# SCH_Stimulus-Shield-_GroeiAcademie-Frame.net
KiCad netlist of a schematic drawn in EasyEDA
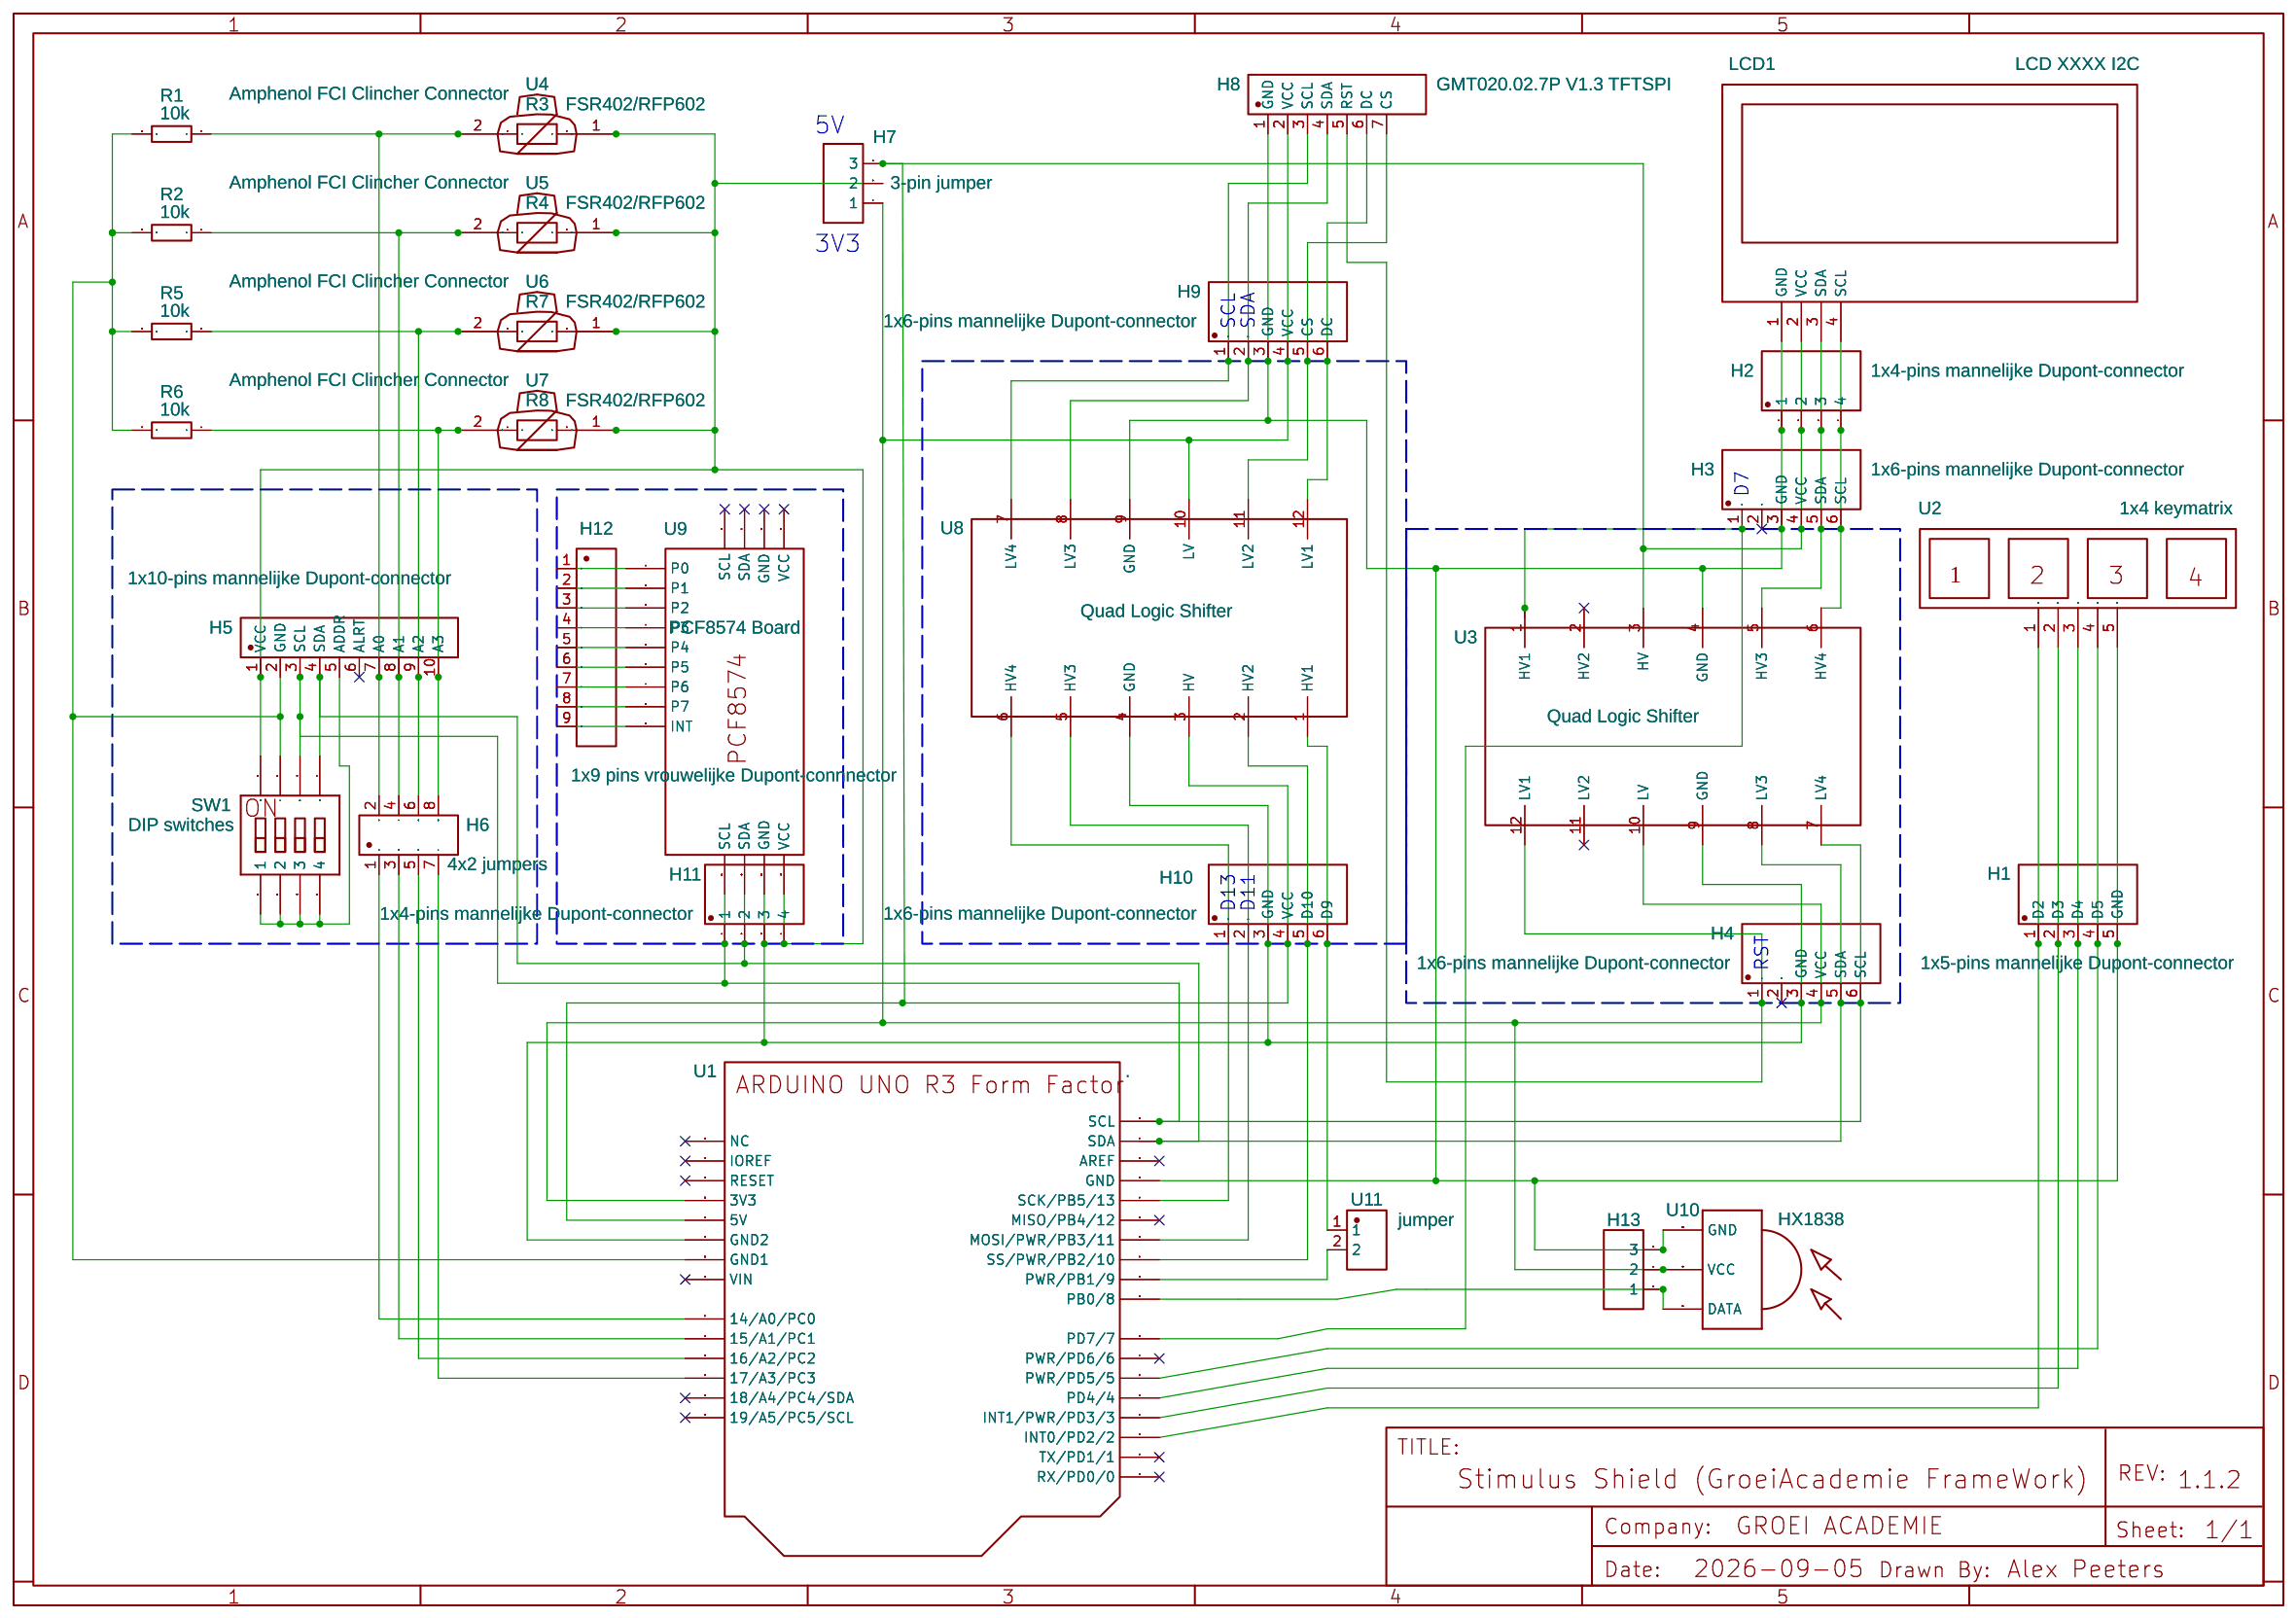
[diagram p0: schematic sheet]

(export (version "E")
  (design (tool "Eeschema 10.0.6"))
  (components
    (comp (ref "H1")
      (value "1x5-pins mannelijke Dupont-connector")
      (fields (field (name "Manufacturer Part") "B-2100S05P-A110") (field (name "Manufacturer") "Ckmtw(灿科盟)"))
      (libsource (lib "") (part "210S-1*5P L=11.6MMGold-plated black"))
    )
    (comp (ref "H2")
      (value "1x4-pins mannelijke Dupont-connector")
      (fields (field (name "Manufacturer Part") "B-2100S04P-A110") (field (name "Manufacturer") "Ckmtw(灿科盟)"))
      (libsource (lib "") (part "Header-Male-2.54_1x4"))
    )
    (comp (ref "H3")
      (value "1x6-pins mannelijke Dupont-connector")
      (fields (field (name "Manufacturer Part") "B-2100S06P-A110") (field (name "Manufacturer") "Ckmtw(灿科盟)"))
      (libsource (lib "") (part "210S-1*6P L=11.6MMGold-plated black_1"))
    )
    (comp (ref "H4")
      (value "1x6-pins mannelijke Dupont-connector")
      (fields (field (name "Manufacturer Part") "B-2100S06P-A110") (field (name "Manufacturer") "Ckmtw(灿科盟)"))
      (libsource (lib "") (part "210S-1*6P L=11.6MMGold-plated black_1"))
    )
    (comp (ref "H5")
      (value "1x10-pins mannelijke Dupont-connector")
      (fields (field (name "Manufacturer Part") "2.54-1*10") (field (name "Manufacturer") "ZHOURI(洲日)"))
      (libsource (lib "") (part "2.54-1*10"))
    )
    (comp (ref "H6")
      (value "4x2 jumpers")
      (fields (field (name "Manufacturer Part") "2.54-2*4P立贴针") (field (name "Manufacturer") "BOOMELE(博穆精密)"))
      (libsource (lib "") (part "2.54-2*4P立贴针"))
    )
    (comp (ref "H7") (value "3-pin jumper") (libsource (lib "") (part "HDR-F-2.54_1x3")))
    (comp (ref "H8")
      (value "GMT020.02.7P V1.3 TFTSPI")
      (fields (field (name "Manufacturer Part") "HDR-M-L12-3+4-1x8P-2.54"))
      (libsource (lib "") (part "PZ254R-11-08P"))
    )
    (comp (ref "H9")
      (value "1x6-pins mannelijke Dupont-connector")
      (fields (field (name "Manufacturer Part") "B-2100S06P-A110") (field (name "Manufacturer") "Ckmtw(灿科盟)"))
      (libsource (lib "") (part "210S-1*6P L=11.6MMGold-plated black_2"))
    )
    (comp (ref "H10")
      (value "1x6-pins mannelijke Dupont-connector")
      (fields (field (name "Manufacturer Part") "B-2100S06P-A110") (field (name "Manufacturer") "Ckmtw(灿科盟)"))
      (libsource (lib "") (part "210S-1*6P L=11.6MMGold-plated black"))
    )
    (comp (ref "H11")
      (value "1x4-pins mannelijke Dupont-connector")
      (fields (field (name "Manufacturer Part") "B-2100S04P-A110") (field (name "Manufacturer") "Ckmtw(灿科盟)"))
      (libsource (lib "") (part "Header-Male-2.54_1x4"))
    )
    (comp (ref "H12")
      (value "1x9 pins vrouwelijke Dupont-connnector")
      (fields
        (field (name "Manufacturer Part") "HX PM1.27-1x9P ZC H2.0")
        (field (name "Manufacturer") "hanxia(韩下)")
      )
      (libsource (lib "") (part "HX PM1.27-1X9P ZC H2.0"))
    )
    (comp (ref "H13") (value "HDR-M-2.54_1x3") (libsource (lib "") (part "HDR-M-2.54_1x3")))
    (comp (ref "LCD1") (value "LCD XXXX I2C") (libsource (lib "") (part "I2CLCD16X2_N")))
    (comp (ref "R1")
      (value "10k")
      (fields (field (name "Manufacturer") "Made in China"))
      (libsource (lib "") (part "330Ω (331) ±5%"))
    )
    (comp (ref "R2")
      (value "10k")
      (fields (field (name "Manufacturer") "Made in China"))
      (libsource (lib "") (part "330Ω (331) ±5%"))
    )
    (comp (ref "R3") (value "FSR402/RFP602") (libsource (lib "") (part "FSR402-OPCION1")))
    (comp (ref "R4") (value "FSR402/RFP602") (libsource (lib "") (part "FSR402-OPCION1")))
    (comp (ref "R5")
      (value "10k")
      (fields (field (name "Manufacturer") "Made in China"))
      (libsource (lib "") (part "330Ω (331) ±5%"))
    )
    (comp (ref "R6")
      (value "10k")
      (fields (field (name "Manufacturer") "Made in China"))
      (libsource (lib "") (part "330Ω (331) ±5%"))
    )
    (comp (ref "R7") (value "FSR402/RFP602") (libsource (lib "") (part "FSR402-OPCION1")))
    (comp (ref "R8") (value "FSR402/RFP602") (libsource (lib "") (part "FSR402-OPCION1")))
    (comp (ref "SW1")
      (value "DIP switches")
      (fields
        (field (name "Manufacturer Part") "DIP switch,Dip Switch,DSWB04LHGET")
        (field (name "Manufacturer") "KE")
      )
      (libsource (lib "") (part "DIP switch 4 Channel"))
    )
    (comp (ref "U1") (value ".") (libsource (lib "") (part "ARDUINO UNO r3")))
    (comp (ref "U2") (value "1x4 keymatrix") (libsource (lib "") (part "Клавиатура 4*4")))
    (comp (ref "U3") (value "Quad Logic Shifter") (libsource (lib "") (part "Quad Logic Shifter_1")))
    (comp (ref "U4")
      (value "Amphenol FCI Clincher Connector")
      (fields (field (name "Manufacturer Part") "AT04-2P-BM02") (field (name "Manufacturer") "Amphenol"))
      (libsource (lib "") (part "AT04-2P"))
    )
    (comp (ref "U5")
      (value "Amphenol FCI Clincher Connector")
      (fields (field (name "Manufacturer Part") "AT04-2P-BM02") (field (name "Manufacturer") "Amphenol"))
      (libsource (lib "") (part "AT04-2P"))
    )
    (comp (ref "U6")
      (value "Amphenol FCI Clincher Connector")
      (fields (field (name "Manufacturer Part") "AT04-2P-BM02") (field (name "Manufacturer") "Amphenol"))
      (libsource (lib "") (part "AT04-2P"))
    )
    (comp (ref "U7")
      (value "Amphenol FCI Clincher Connector")
      (fields (field (name "Manufacturer Part") "AT04-2P-BM02") (field (name "Manufacturer") "Amphenol"))
      (libsource (lib "") (part "AT04-2P"))
    )
    (comp (ref "U8") (value "Quad Logic Shifter") (libsource (lib "") (part "Quad Logic Shifter")))
    (comp (ref "U9")
      (value "PCF8574 Board")
      (fields
        (field (name "Manufacturer Part") "PCF8574 IO Expansion Board")
        (field (name "Manufacturer") "WaveShare")
      )
      (libsource (lib "") (part "PCF8574 IO Expansion Board"))
    )
    (comp (ref "U10") (value "HX1838") (libsource (lib "") (part "IR_HX1838")))
    (comp (ref "U11")
      (value "jumper")
      (fields (field (name "Manufacturer Part") "Jumper2"))
      (libsource (lib "") (part "JUMPER2"))
    )
  )
  (nets
    (net (code "1") (name "Net-(H1-D2)") (class "Default")
      (node (ref "H1") (pin "1") (pinfunction "D2_1") (pintype "unspecified"))
      (node (ref "U1") (pin "3") (pinfunction "INT0/PD2/2_3") (pintype "unspecified"))
      (node (ref "U2") (pin "1") (pinfunction "C1_1") (pintype "unspecified"))
    )
    (net (code "2") (name "Net-(H1-D3)") (class "Default")
      (node (ref "H1") (pin "2") (pinfunction "D3_2") (pintype "unspecified"))
      (node (ref "U1") (pin "4") (pinfunction "INT1/PWR/PD3/3_4") (pintype "unspecified"))
      (node (ref "U2") (pin "2") (pinfunction "C2_2") (pintype "unspecified"))
    )
    (net (code "3") (name "Net-(H1-D4)") (class "Default")
      (node (ref "H1") (pin "3") (pinfunction "D4_3") (pintype "unspecified"))
      (node (ref "U1") (pin "5") (pinfunction "PD4/4_5") (pintype "unspecified"))
      (node (ref "U2") (pin "3") (pinfunction "C3_3") (pintype "unspecified"))
    )
    (net (code "4") (name "Net-(H1-D5)") (class "Default")
      (node (ref "H1") (pin "4") (pinfunction "D5_4") (pintype "unspecified"))
      (node (ref "U1") (pin "6") (pinfunction "PWR/PD5/5_6") (pintype "unspecified"))
      (node (ref "U2") (pin "4") (pinfunction "R1_4") (pintype "unspecified"))
    )
    (net (code "5") (name "Net-(H1-GND)") (class "Default")
      (node (ref "H1") (pin "5") (pinfunction "GND_5") (pintype "unspecified"))
      (node (ref "H13") (pin "3") (pinfunction "3_3") (pintype "input"))
      (node (ref "H2") (pin "1") (pinfunction "1_1") (pintype "unspecified"))
      (node (ref "H3") (pin "3") (pinfunction "GND_3") (pintype "unspecified"))
      (node (ref "H8") (pin "1") (pinfunction "GND_1") (pintype "unspecified"))
      (node (ref "H9") (pin "3") (pinfunction "GND_3") (pintype "unspecified"))
      (node (ref "LCD1") (pin "1") (pinfunction "GND_1") (pintype "unspecified"))
      (node (ref "U1") (pin "15") (pinfunction "GND_15") (pintype "passive"))
      (node (ref "U10") (pin "GND") (pinfunction "GND_GND") (pintype "unspecified"))
      (node (ref "U2") (pin "5") (pinfunction "R2_5") (pintype "unspecified"))
      (node (ref "U3") (pin "4") (pinfunction "GND_4") (pintype "unspecified"))
      (node (ref "U8") (pin "9") (pinfunction "GND_9") (pintype "unspecified"))
    )
    (net (code "6") (name "Net-(H3-SCL)") (class "Default")
      (node (ref "H2") (pin "4") (pinfunction "4_4") (pintype "unspecified"))
      (node (ref "H3") (pin "6") (pinfunction "SCL_6") (pintype "unspecified"))
      (node (ref "LCD1") (pin "4") (pinfunction "SCL_4") (pintype "unspecified"))
      (node (ref "U3") (pin "6") (pinfunction "HV4_6") (pintype "unspecified"))
    )
    (net (code "7") (name "Net-(H3-SDA)") (class "Default")
      (node (ref "H2") (pin "3") (pinfunction "3_3") (pintype "unspecified"))
      (node (ref "H3") (pin "5") (pinfunction "SDA_5") (pintype "unspecified"))
      (node (ref "LCD1") (pin "3") (pinfunction "SDA_3") (pintype "unspecified"))
      (node (ref "U3") (pin "5") (pinfunction "HV3_5") (pintype "unspecified"))
    )
    (net (code "8") (name "Net-(H4-SCL)") (class "Default")
      (node (ref "H11") (pin "1") (pinfunction "1_1") (pintype "unspecified"))
      (node (ref "H4") (pin "6") (pinfunction "SCL_6") (pintype "unspecified"))
      (node (ref "H5") (pin "3") (pinfunction "SCL_3") (pintype "unspecified"))
      (node (ref "SW1") (pin "3I") (pinfunction "6_3I") (pintype "input"))
      (node (ref "U1") (pin "18") (pinfunction "SCL_18") (pintype "unspecified"))
      (node (ref "U3") (pin "7") (pinfunction "LV4_7") (pintype "unspecified"))
      (node (ref "U9") (pin "SCL") (pinfunction "SCL_SCL") (pintype "unspecified"))
    )
    (net (code "9") (name "Net-(H4-SDA)") (class "Default")
      (node (ref "H11") (pin "2") (pinfunction "2_2") (pintype "unspecified"))
      (node (ref "H4") (pin "5") (pinfunction "SDA_5") (pintype "unspecified"))
      (node (ref "H5") (pin "4") (pinfunction "SDA_4") (pintype "unspecified"))
      (node (ref "SW1") (pin "4I") (pinfunction "5_4I") (pintype "input"))
      (node (ref "U1") (pin "17") (pinfunction "SDA_17") (pintype "unspecified"))
      (node (ref "U3") (pin "8") (pinfunction "LV3_8") (pintype "unspecified"))
      (node (ref "U9") (pin "SDA") (pinfunction "SDA_SDA") (pintype "unspecified"))
    )
    (net (code "10") (name "Net-(H4-VCC)") (class "Default")
      (node (ref "H13") (pin "2") (pinfunction "2_2") (pintype "input"))
      (node (ref "H4") (pin "4") (pinfunction "VCC_4") (pintype "unspecified"))
      (node (ref "H7") (pin "1") (pinfunction "1_1") (pintype "input"))
      (node (ref "H8") (pin "2") (pinfunction "VCC_2") (pintype "unspecified"))
      (node (ref "H9") (pin "4") (pinfunction "VCC_4") (pintype "unspecified"))
      (node (ref "U1") (pin "29") (pinfunction "3V3_29") (pintype "passive"))
      (node (ref "U10") (pin "VCC") (pinfunction "VCC_VCC") (pintype "unspecified"))
      (node (ref "U3") (pin "10") (pinfunction "LV_10") (pintype "unspecified"))
      (node (ref "U8") (pin "10") (pinfunction "LV_10") (pintype "unspecified"))
    )
    (net (code "11") (name "Net-(H5-A0)") (class "Default")
      (node (ref "H5") (pin "7") (pinfunction "A0_7") (pintype "unspecified"))
      (node (ref "H6") (pin "2") (pinfunction "2_2") (pintype "unspecified"))
      (node (ref "R1") (pin "1") (pinfunction "1_1") (pintype "unspecified"))
      (node (ref "R3") (pin "1") (pinfunction "1_1") (pintype "unspecified"))
      (node (ref "U4") (pin "2") (pinfunction "2_2") (pintype "unspecified"))
    )
    (net (code "12") (name "Net-(H5-A1)") (class "Default")
      (node (ref "H5") (pin "8") (pinfunction "A1_8") (pintype "unspecified"))
      (node (ref "H6") (pin "4") (pinfunction "4_4") (pintype "unspecified"))
      (node (ref "R2") (pin "1") (pinfunction "1_1") (pintype "unspecified"))
      (node (ref "R4") (pin "1") (pinfunction "1_1") (pintype "unspecified"))
      (node (ref "U5") (pin "2") (pinfunction "2_2") (pintype "unspecified"))
    )
    (net (code "13") (name "Net-(H5-A2)") (class "Default")
      (node (ref "H5") (pin "9") (pinfunction "A2_9") (pintype "unspecified"))
      (node (ref "H6") (pin "6") (pinfunction "6_6") (pintype "unspecified"))
      (node (ref "R5") (pin "1") (pinfunction "1_1") (pintype "unspecified"))
      (node (ref "R7") (pin "1") (pinfunction "1_1") (pintype "unspecified"))
      (node (ref "U6") (pin "2") (pinfunction "2_2") (pintype "unspecified"))
    )
    (net (code "14") (name "Net-(H5-A3)") (class "Default")
      (node (ref "H5") (pin "10") (pinfunction "A3_10") (pintype "unspecified"))
      (node (ref "H6") (pin "8") (pinfunction "8_8") (pintype "unspecified"))
      (node (ref "R6") (pin "1") (pinfunction "1_1") (pintype "unspecified"))
      (node (ref "R8") (pin "1") (pinfunction "1_1") (pintype "unspecified"))
      (node (ref "U7") (pin "2") (pinfunction "2_2") (pintype "unspecified"))
    )
    (net (code "15") (name "Net-(H5-ADDR)") (class "Default")
      (node (ref "H5") (pin "5") (pinfunction "ADDR_5") (pintype "unspecified"))
      (node (ref "SW1") (pin "1O") (pinfunction "1_1O") (pintype "input"))
      (node (ref "SW1") (pin "2O") (pinfunction "2_2O") (pintype "input"))
      (node (ref "SW1") (pin "3O") (pinfunction "3_3O") (pintype "input"))
      (node (ref "SW1") (pin "4O") (pinfunction "4_4O") (pintype "input"))
    )
    (net (code "16") (name "Net-(H5-GND)") (class "Default")
      (node (ref "H5") (pin "2") (pinfunction "GND_2") (pintype "unspecified"))
      (node (ref "R1") (pin "2") (pinfunction "2_2") (pintype "unspecified"))
      (node (ref "R2") (pin "2") (pinfunction "2_2") (pintype "unspecified"))
      (node (ref "R5") (pin "2") (pinfunction "2_2") (pintype "unspecified"))
      (node (ref "R6") (pin "2") (pinfunction "2_2") (pintype "unspecified"))
      (node (ref "SW1") (pin "2I") (pinfunction "7_2I") (pintype "input"))
      (node (ref "U1") (pin "26") (pinfunction "GND1_26") (pintype "passive"))
    )
    (net (code "17") (name "Net-(H5-VCC)") (class "Default")
      (node (ref "H11") (pin "4") (pinfunction "4_4") (pintype "unspecified"))
      (node (ref "H5") (pin "1") (pinfunction "VCC_1") (pintype "unspecified"))
      (node (ref "H7") (pin "2") (pinfunction "2_2") (pintype "input"))
      (node (ref "R3") (pin "2") (pinfunction "2_2") (pintype "unspecified"))
      (node (ref "R4") (pin "2") (pinfunction "2_2") (pintype "unspecified"))
      (node (ref "R7") (pin "2") (pinfunction "2_2") (pintype "unspecified"))
      (node (ref "R8") (pin "2") (pinfunction "2_2") (pintype "unspecified"))
      (node (ref "SW1") (pin "1I") (pinfunction "8_1I") (pintype "input"))
      (node (ref "U4") (pin "1") (pinfunction "1_1") (pintype "unspecified"))
      (node (ref "U5") (pin "1") (pinfunction "1_1") (pintype "unspecified"))
      (node (ref "U6") (pin "1") (pinfunction "1_1") (pintype "unspecified"))
      (node (ref "U7") (pin "1") (pinfunction "1_1") (pintype "unspecified"))
      (node (ref "U9") (pin "VCC") (pinfunction "VCC_VCC") (pintype "unspecified"))
    )
    (net (code "18") (name "Net-(H8-CS)") (class "Default")
      (node (ref "H8") (pin "7") (pinfunction "CS_7") (pintype "unspecified"))
      (node (ref "H9") (pin "5") (pinfunction "CS_5") (pintype "unspecified"))
      (node (ref "U8") (pin "11") (pinfunction "LV2_11") (pintype "unspecified"))
    )
    (net (code "19") (name "Net-(H8-DC)") (class "Default")
      (node (ref "H8") (pin "6") (pinfunction "DC_6") (pintype "unspecified"))
      (node (ref "H9") (pin "6") (pinfunction "DC_6") (pintype "unspecified"))
      (node (ref "U8") (pin "12") (pinfunction "LV1_12") (pintype "unspecified"))
    )
    (net (code "20") (name "Net-(H8-RST)") (class "Default")
      (node (ref "H4") (pin "1") (pinfunction "1_1") (pintype "unspecified"))
      (node (ref "H8") (pin "5") (pinfunction "RST_5") (pintype "unspecified"))
      (node (ref "U3") (pin "12") (pinfunction "LV1_12") (pintype "unspecified"))
    )
    (net (code "21") (name "Net-(H8-SCL)") (class "Default")
      (node (ref "H8") (pin "3") (pinfunction "SCL_3") (pintype "unspecified"))
      (node (ref "H9") (pin "1") (pinfunction "1_1") (pintype "unspecified"))
      (node (ref "U8") (pin "7") (pinfunction "LV4_7") (pintype "unspecified"))
    )
    (net (code "22") (name "Net-(H8-SDA)") (class "Default")
      (node (ref "H8") (pin "4") (pinfunction "SDA_4") (pintype "unspecified"))
      (node (ref "H9") (pin "2") (pinfunction "2_2") (pintype "unspecified"))
      (node (ref "U8") (pin "8") (pinfunction "LV3_8") (pintype "unspecified"))
    )
    (net (code "23") (name "Net-(H10-D9)") (class "Default")
      (node (ref "H10") (pin "6") (pinfunction "D9_6") (pintype "unspecified"))
      (node (ref "U11") (pin "1") (pinfunction "1_1") (pintype "unspecified"))
      (node (ref "U8") (pin "1") (pinfunction "HV1_1") (pintype "unspecified"))
    )
    (net (code "24") (name "Net-(H10-D10)") (class "Default")
      (node (ref "H10") (pin "5") (pinfunction "D10_5") (pintype "unspecified"))
      (node (ref "U1") (pin "11") (pinfunction "SS/PWR/PB2/10_11") (pintype "unspecified"))
      (node (ref "U8") (pin "2") (pinfunction "HV2_2") (pintype "unspecified"))
    )
    (net (code "25") (name "Net-(H10-GND)") (class "Default")
      (node (ref "H10") (pin "3") (pinfunction "GND_3") (pintype "unspecified"))
      (node (ref "H11") (pin "3") (pinfunction "3_3") (pintype "unspecified"))
      (node (ref "H4") (pin "3") (pinfunction "GND_3") (pintype "unspecified"))
      (node (ref "U1") (pin "27") (pinfunction "GND2_27") (pintype "passive"))
      (node (ref "U3") (pin "9") (pinfunction "GND_9") (pintype "unspecified"))
      (node (ref "U8") (pin "4") (pinfunction "GND_4") (pintype "unspecified"))
      (node (ref "U9") (pin "GND") (pinfunction "GND_GND") (pintype "unspecified"))
    )
    (net (code "26") (name "Net-(H10-VCC)") (class "Default")
      (node (ref "H10") (pin "4") (pinfunction "VCC_4") (pintype "unspecified"))
      (node (ref "H2") (pin "2") (pinfunction "2_2") (pintype "unspecified"))
      (node (ref "H3") (pin "4") (pinfunction "VCC_4") (pintype "unspecified"))
      (node (ref "H7") (pin "3") (pinfunction "3_3") (pintype "input"))
      (node (ref "LCD1") (pin "2") (pinfunction "VCC_2") (pintype "unspecified"))
      (node (ref "U1") (pin "28") (pinfunction "5V_28") (pintype "passive"))
      (node (ref "U3") (pin "3") (pinfunction "HV_3") (pintype "unspecified"))
      (node (ref "U8") (pin "3") (pinfunction "HV_3") (pintype "unspecified"))
    )
    (net (code "27") (name "Net-(U1-14{slash}A0{slash}PC0)") (class "Default")
      (node (ref "H6") (pin "1") (pinfunction "1_1") (pintype "unspecified"))
      (node (ref "U1") (pin "24") (pinfunction "14/A0/PC0_24") (pintype "unspecified"))
    )
    (net (code "28") (name "Net-(U1-15{slash}A1{slash}PC1)") (class "Default")
      (node (ref "H6") (pin "3") (pinfunction "3_3") (pintype "unspecified"))
      (node (ref "U1") (pin "23") (pinfunction "15/A1/PC1_23") (pintype "unspecified"))
    )
    (net (code "29") (name "Net-(U1-16{slash}A2{slash}PC2)") (class "Default")
      (node (ref "H6") (pin "5") (pinfunction "5_5") (pintype "unspecified"))
      (node (ref "U1") (pin "22") (pinfunction "16/A2/PC2_22") (pintype "unspecified"))
    )
    (net (code "30") (name "Net-(U1-17{slash}A3{slash}PC3)") (class "Default")
      (node (ref "H6") (pin "7") (pinfunction "7_7") (pintype "unspecified"))
      (node (ref "U1") (pin "21") (pinfunction "17/A3/PC3_21") (pintype "unspecified"))
    )
    (net (code "31") (name "Net-(U1-MOSI{slash}PWR{slash}PB3{slash}11)") (class "Default")
      (node (ref "H10") (pin "2") (pinfunction "2_2") (pintype "unspecified"))
      (node (ref "U1") (pin "12") (pinfunction "MOSI/PWR/PB3/11_12") (pintype "unspecified"))
    )
    (net (code "32") (name "Net-(U1-PB0{slash}8)") (class "Default")
      (node (ref "H13") (pin "1") (pinfunction "1_1") (pintype "input"))
      (node (ref "U1") (pin "9") (pinfunction "PB0/8_9") (pintype "unspecified"))
      (node (ref "U10") (pin "DATA") (pinfunction "DATA_DATA") (pintype "unspecified"))
    )
    (net (code "33") (name "Net-(U1-PD7{slash}7)") (class "Default")
      (node (ref "H3") (pin "1") (pinfunction "1_1") (pintype "unspecified"))
      (node (ref "U1") (pin "8") (pinfunction "PD7/7_8") (pintype "unspecified"))
      (node (ref "U3") (pin "1") (pinfunction "HV1_1") (pintype "unspecified"))
    )
    (net (code "34") (name "Net-(U1-PWR{slash}PB1{slash}9)") (class "Default")
      (node (ref "U1") (pin "10") (pinfunction "PWR/PB1/9_10") (pintype "unspecified"))
      (node (ref "U11") (pin "2") (pinfunction "2_2") (pintype "unspecified"))
    )
    (net (code "35") (name "Net-(U1-SCK{slash}PB5{slash}13)") (class "Default")
      (node (ref "H10") (pin "1") (pinfunction "1_1") (pintype "unspecified"))
      (node (ref "U1") (pin "14") (pinfunction "SCK/PB5/13_14") (pintype "unspecified"))
    )
    (net (code "36") (name "Net-(U9-INT)") (class "Default")
      (node (ref "H12") (pin "9") (pinfunction "9_9") (pintype "unspecified"))
      (node (ref "U9") (pin "9") (pinfunction "INT_9") (pintype "unspecified"))
    )
    (net (code "37") (name "Net-(U9-P0)") (class "Default")
      (node (ref "H12") (pin "1") (pinfunction "1_1") (pintype "unspecified"))
      (node (ref "U9") (pin "1") (pinfunction "P0_1") (pintype "unspecified"))
    )
    (net (code "38") (name "Net-(U9-P1)") (class "Default")
      (node (ref "H12") (pin "2") (pinfunction "2_2") (pintype "unspecified"))
      (node (ref "U9") (pin "2") (pinfunction "P1_2") (pintype "unspecified"))
    )
    (net (code "39") (name "Net-(U9-P2)") (class "Default")
      (node (ref "H12") (pin "3") (pinfunction "3_3") (pintype "unspecified"))
      (node (ref "U9") (pin "3") (pinfunction "P2_3") (pintype "unspecified"))
    )
    (net (code "40") (name "Net-(U9-P3)") (class "Default")
      (node (ref "H12") (pin "4") (pinfunction "4_4") (pintype "unspecified"))
      (node (ref "U9") (pin "4") (pinfunction "P3_4") (pintype "unspecified"))
    )
    (net (code "41") (name "Net-(U9-P4)") (class "Default")
      (node (ref "H12") (pin "5") (pinfunction "5_5") (pintype "unspecified"))
      (node (ref "U9") (pin "5") (pinfunction "P4_5") (pintype "unspecified"))
    )
    (net (code "42") (name "Net-(U9-P5)") (class "Default")
      (node (ref "H12") (pin "6") (pinfunction "6_6") (pintype "unspecified"))
      (node (ref "U9") (pin "6") (pinfunction "P5_6") (pintype "unspecified"))
    )
    (net (code "43") (name "Net-(U9-P6)") (class "Default")
      (node (ref "H12") (pin "7") (pinfunction "7_7") (pintype "unspecified"))
      (node (ref "U9") (pin "7") (pinfunction "P6_7") (pintype "unspecified"))
    )
    (net (code "44") (name "Net-(U9-P7)") (class "Default")
      (node (ref "H12") (pin "8") (pinfunction "8_8") (pintype "unspecified"))
      (node (ref "U9") (pin "8") (pinfunction "P7_8") (pintype "unspecified"))
    )
    (net (code "45") (name "unconnected-(H3-Pad2)") (class "Default")
      (node (ref "H3") (pin "2") (pinfunction "2_2") (pintype "unspecified+no_connect"))
    )
    (net (code "46") (name "unconnected-(H4-Pad2)") (class "Default")
      (node (ref "H4") (pin "2") (pinfunction "2_2") (pintype "unspecified+no_connect"))
    )
    (net (code "47") (name "unconnected-(H5-ALRT-Pad6)") (class "Default")
      (node (ref "H5") (pin "6") (pinfunction "ALRT_6") (pintype "unspecified+no_connect"))
    )
    (net (code "48") (name "unconnected-(U1-18{slash}A4{slash}PC4{slash}SDA-Pad20)") (class "Default")
      (node (ref "U1") (pin "20") (pinfunction "18/A4/PC4/SDA_20") (pintype "unspecified+no_connect"))
    )
    (net (code "49") (name "unconnected-(U1-19{slash}A5{slash}PC5{slash}SCL-Pad19)") (class "Default")
      (node (ref "U1") (pin "19") (pinfunction "19/A5/PC5/SCL_19") (pintype "unspecified+no_connect"))
    )
    (net (code "50") (name "unconnected-(U1-AREF-Pad16)") (class "Default")
      (node (ref "U1") (pin "16") (pinfunction "AREF_16") (pintype "unspecified+no_connect"))
    )
    (net (code "51") (name "unconnected-(U1-IOREF-Pad31)") (class "Default")
      (node (ref "U1") (pin "31") (pinfunction "IOREF_31") (pintype "unspecified+no_connect"))
    )
    (net (code "52") (name "unconnected-(U1-MISO{slash}PB4{slash}12-Pad13)") (class "Default")
      (node (ref "U1") (pin "13") (pinfunction "MISO/PB4/12_13") (pintype "unspecified+no_connect"))
    )
    (net (code "53") (name "unconnected-(U1-NC-Pad32)") (class "Default")
      (node (ref "U1") (pin "32") (pinfunction "NC_32") (pintype "unspecified+no_connect"))
    )
    (net (code "54") (name "unconnected-(U1-PWR{slash}PD6{slash}6-Pad7)") (class "Default")
      (node (ref "U1") (pin "7") (pinfunction "PWR/PD6/6_7") (pintype "unspecified+no_connect"))
    )
    (net (code "55") (name "unconnected-(U1-RESET-Pad30)") (class "Default")
      (node (ref "U1") (pin "30") (pinfunction "RESET_30") (pintype "unspecified+no_connect"))
    )
    (net (code "56") (name "unconnected-(U1-RX{slash}PD0{slash}0-Pad1)") (class "Default")
      (node (ref "U1") (pin "1") (pinfunction "RX/PD0/0_1") (pintype "unspecified+no_connect"))
    )
    (net (code "57") (name "unconnected-(U1-TX{slash}PD1{slash}1-Pad2)") (class "Default")
      (node (ref "U1") (pin "2") (pinfunction "TX/PD1/1_2") (pintype "unspecified+no_connect"))
    )
    (net (code "58") (name "unconnected-(U1-VIN-Pad25)") (class "Default")
      (node (ref "U1") (pin "25") (pinfunction "VIN_25") (pintype "passive+no_connect"))
    )
    (net (code "59") (name "unconnected-(U3-HV2-Pad2)") (class "Default")
      (node (ref "U3") (pin "2") (pinfunction "HV2_2") (pintype "unspecified+no_connect"))
    )
    (net (code "60") (name "unconnected-(U3-LV2-Pad11)") (class "Default")
      (node (ref "U3") (pin "11") (pinfunction "LV2_11") (pintype "unspecified+no_connect"))
    )
    (net (code "61") (name "unconnected-(U8-HV3-Pad5)") (class "Default")
      (node (ref "U8") (pin "5") (pinfunction "HV3_5") (pintype "unspecified"))
    )
    (net (code "62") (name "unconnected-(U8-HV4-Pad6)") (class "Default")
      (node (ref "U8") (pin "6") (pinfunction "HV4_6") (pintype "unspecified"))
    )
    (net (code "63") (name "unconnected-(U9-GND-Pad12)") (class "Default")
      (node (ref "U9") (pin "12") (pinfunction "GND_12") (pintype "unspecified+no_connect"))
    )
    (net (code "64") (name "unconnected-(U9-SCL-Pad10)") (class "Default")
      (node (ref "U9") (pin "10") (pinfunction "SCL_10") (pintype "unspecified+no_connect"))
    )
    (net (code "65") (name "unconnected-(U9-SDA-Pad11)") (class "Default")
      (node (ref "U9") (pin "11") (pinfunction "SDA_11") (pintype "unspecified+no_connect"))
    )
    (net (code "66") (name "unconnected-(U9-VCC-Pad13)") (class "Default")
      (node (ref "U9") (pin "13") (pinfunction "VCC_13") (pintype "unspecified+no_connect"))
    )
  )
)
